# design.net
KiCad netlist of a schematic drawn in Altium Designer
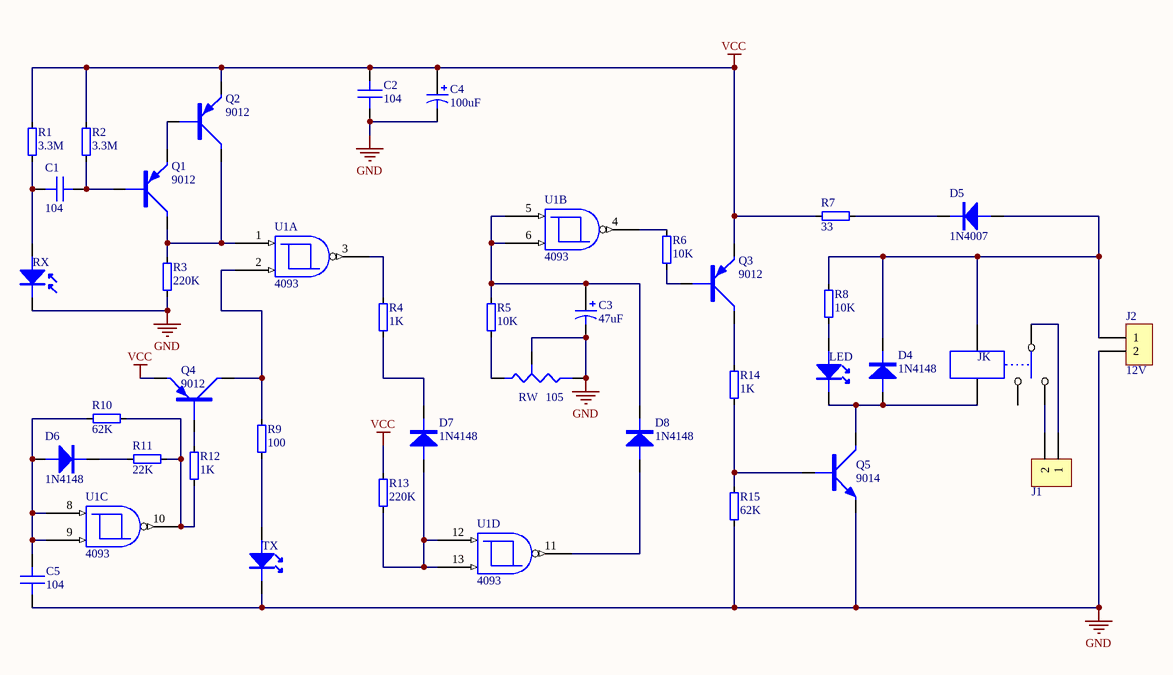
[diagram p0: 红外感应开关.SchDoc]

(export (version "E")
  (design (tool "Eeschema 10.0.6"))
  (components
    (comp (ref "C1")
      (value "CAP")
      (footprint "104独石电容")
      (description "Capacitor，电容")
      (fields (field (name "ALTIUM_UNNAMED_1") "104"))
      (libsource (lib "Backup of 元件") (part "CAP"))
    )
    (comp (ref "C2")
      (value "CAP")
      (footprint "104独石电容")
      (description "Capacitor，电容")
      (fields (field (name "ALTIUM_UNNAMED_1") "104"))
      (libsource (lib "Backup of 元件") (part "CAP"))
    )
    (comp (ref "C3")
      (value "47uF")
      (footprint "47uf")
      (description "Polarized Capacitor (Radial)")
      (fields (field (name "Comment") "Cap Pol1") (field (name "PUBLISHER") "Altium Limited"))
      (libsource (lib "Miscellaneous Devices") (part "Cap Pol1"))
    )
    (comp (ref "C4")
      (value "100uF")
      (footprint "电容D=8mm")
      (description "Polarized Capacitor (Radial)")
      (fields (field (name "Comment") "Cap Pol1") (field (name "PUBLISHER") "Altium Limited"))
      (libsource (lib "Miscellaneous Devices") (part "Cap Pol1"))
    )
    (comp (ref "C5")
      (value "CAP")
      (footprint "104独石电容")
      (description "Capacitor，电容")
      (fields (field (name "ALTIUM_UNNAMED_1") "104"))
      (libsource (lib "Backup of 元件") (part "CAP"))
    )
    (comp (ref "D4") (value "1N4148") (footprint "1N4007") (libsource (lib "DIODE") (part "DIODE")))
    (comp (ref "D5") (value "1N4007") (footprint "1N4007") (libsource (lib "") (part "DIODE_1")))
    (comp (ref "D6") (value "1N4148") (footprint "1N4148") (libsource (lib "") (part "DIODE_2")))
    (comp (ref "D7") (value "1N4148") (footprint "1N4148") (libsource (lib "DIODE") (part "DIODE")))
    (comp (ref "D8") (value "1N4148") (footprint "1N4148") (libsource (lib "DIODE") (part "DIODE")))
    (comp (ref "J1")
      (value "CON2")
      (footprint "KF-5.08")
      (description "Connector")
      (libsource (lib "") (part "CON2_1"))
    )
    (comp (ref "J2")
      (value "12V")
      (footprint "KF-5.08")
      (description "Connector")
      (libsource (lib "MyInt_Lib") (part "CON2"))
    )
    (comp (ref "JK") (value "RWLAY-SPDT") (footprint "继电器") (libsource (lib "J继电器") (part "RWLAY-SPDT")))
    (comp (ref "LED") (value "FA") (footprint "DIODE") (libsource (lib "DIODE") (part "LED")))
    (comp (ref "Q1")
      (value "9012")
      (footprint "8050-TO-92")
      (description "PNP Transistor")
      (libsource (lib "Backup of 元件") (part "9012"))
    )
    (comp (ref "Q2")
      (value "9012")
      (footprint "8050-TO-92")
      (description "PNP Transistor")
      (libsource (lib "Backup of 元件") (part "9012"))
    )
    (comp (ref "Q3")
      (value "9012")
      (footprint "8050-TO-92")
      (description "PNP Transistor")
      (libsource (lib "Backup of 元件") (part "9012"))
    )
    (comp (ref "Q4")
      (value "9012")
      (footprint "8050-TO-92")
      (description "PNP Transistor")
      (libsource (lib "") (part "9012_1"))
    )
    (comp (ref "Q5")
      (value "9014")
      (footprint "8050-TO-92")
      (description "NPN Transistor")
      (libsource (lib "复件 Previous Backup of  元件") (part "9014"))
    )
    (comp (ref "R1")
      (value "RES")
      (footprint "RES-0.25W")
      (fields (field (name "ALTIUM_UNNAMED_1") "3.3M"))
      (libsource (lib "MyInt_Lib") (part "RES"))
    )
    (comp (ref "R2")
      (value "RES")
      (footprint "RES-0.25W")
      (fields (field (name "ALTIUM_UNNAMED_1") "3.3M"))
      (libsource (lib "MyInt_Lib") (part "RES"))
    )
    (comp (ref "R3")
      (value "RES")
      (footprint "RES-0.25W")
      (fields (field (name "ALTIUM_UNNAMED_1") "220K"))
      (libsource (lib "MyInt_Lib") (part "RES"))
    )
    (comp (ref "R4")
      (value "RES")
      (footprint "RES-0.25W")
      (fields (field (name "ALTIUM_UNNAMED_1") "1K"))
      (libsource (lib "MyInt_Lib") (part "RES"))
    )
    (comp (ref "R5")
      (value "RES")
      (footprint "RES-0.25W")
      (fields (field (name "ALTIUM_UNNAMED_1") "10K"))
      (libsource (lib "MyInt_Lib") (part "RES"))
    )
    (comp (ref "R6")
      (value "RES")
      (footprint "RES-0.25W")
      (fields (field (name "ALTIUM_UNNAMED_1") "10K"))
      (libsource (lib "MyInt_Lib") (part "RES"))
    )
    (comp (ref "R7")
      (value "RES")
      (footprint "RES-1W")
      (fields (field (name "ALTIUM_UNNAMED_1") "33"))
      (libsource (lib "MyInt_Lib") (part "RES"))
    )
    (comp (ref "R8")
      (value "RES")
      (footprint "RES-0.25W")
      (fields (field (name "ALTIUM_UNNAMED_1") "10K"))
      (libsource (lib "MyInt_Lib") (part "RES"))
    )
    (comp (ref "R9")
      (value "RES")
      (footprint "RES-1W")
      (fields (field (name "ALTIUM_UNNAMED_1") "100"))
      (libsource (lib "MyInt_Lib") (part "RES"))
    )
    (comp (ref "R10")
      (value "RES")
      (footprint "RES-0.25W")
      (fields (field (name "ALTIUM_UNNAMED_1") "62K"))
      (libsource (lib "MyInt_Lib") (part "RES"))
    )
    (comp (ref "R11")
      (value "RES")
      (footprint "RES-0.25W")
      (fields (field (name "ALTIUM_UNNAMED_1") "22K"))
      (libsource (lib "MyInt_Lib") (part "RES"))
    )
    (comp (ref "R12")
      (value "RES")
      (footprint "RES-0.25W")
      (fields (field (name "ALTIUM_UNNAMED_1") "1K"))
      (libsource (lib "MyInt_Lib") (part "RES"))
    )
    (comp (ref "R13")
      (value "RES")
      (footprint "RES-0.25W")
      (fields (field (name "ALTIUM_UNNAMED_1") "220K"))
      (libsource (lib "MyInt_Lib") (part "RES"))
    )
    (comp (ref "R14")
      (value "RES")
      (footprint "RES-0.25W")
      (fields (field (name "ALTIUM_UNNAMED_1") "1K"))
      (libsource (lib "MyInt_Lib") (part "RES"))
    )
    (comp (ref "R15")
      (value "RES")
      (footprint "RES-0.25W")
      (fields (field (name "ALTIUM_UNNAMED_1") "62K"))
      (libsource (lib "MyInt_Lib") (part "RES"))
    )
    (comp (ref "RW")
      (value "RESISTOR TAPPED")
      (footprint "RVR-2")
      (fields (field (name "ALTIUM_UNNAMED_1") "105"))
      (libsource (lib "MyInt_Lib") (part "RESISTOR TAPPED"))
    )
    (comp (ref "RX")
      (value "SHOU")
      (footprint "红外接受管")
      (description "Photosensitive Diode")
      (libsource (lib "DIODE") (part "PHOTO"))
    )
    (comp (ref "TX") (value "FA") (footprint "DIODE0.1") (libsource (lib "DIODE") (part "LED")))
    (comp (ref "U1") (value "4093") (footprint "DIP-14") (libsource (lib "4000 CMOS") (part "4093")))
  )
  (nets
    (net (code "1") (name "GND") (class "Default")
      (node (ref "C2") (pin "2") (pinfunction "2_2") (pintype "passive"))
      (node (ref "C3") (pin "2") (pinfunction "2_2") (pintype "passive"))
      (node (ref "C4") (pin "2") (pinfunction "2_2") (pintype "passive"))
      (node (ref "C5") (pin "2") (pinfunction "2_2") (pintype "passive"))
      (node (ref "J2") (pin "2") (pinfunction "2_2") (pintype "passive"))
      (node (ref "Q5") (pin "1") (pinfunction "E_1") (pintype "passive"))
      (node (ref "R15") (pin "2") (pinfunction "2_2") (pintype "passive"))
      (node (ref "R3") (pin "2") (pinfunction "2_2") (pintype "passive"))
      (node (ref "RW") (pin "2") (pinfunction "2_2") (pintype "passive"))
      (node (ref "RW") (pin "3") (pinfunction "3_3") (pintype "passive"))
      (node (ref "RX") (pin "2") (pinfunction "2_2") (pintype "passive"))
      (node (ref "TX") (pin "2") (pinfunction "2_2") (pintype "passive"))
      (node (ref "U1") (pin "7") (pinfunction "GND_7") (pintype "power_in"))
    )
    (net (code "2") (name "Net-(C1-Pad2)") (class "Default")
      (node (ref "C1") (pin "2") (pinfunction "2_2") (pintype "passive"))
      (node (ref "R1") (pin "2") (pinfunction "2_2") (pintype "passive"))
      (node (ref "RX") (pin "1") (pinfunction "1_1") (pintype "passive"))
    )
    (net (code "3") (name "Net-(C3-Pad1)") (class "Default")
      (node (ref "C3") (pin "1") (pinfunction "1_1") (pintype "passive"))
      (node (ref "D8") (pin "2") (pinfunction "2_2") (pintype "passive"))
      (node (ref "R5") (pin "1") (pinfunction "1_1") (pintype "passive"))
      (node (ref "U1") (pin "5") (pintype "input"))
      (node (ref "U1") (pin "6") (pintype "input"))
    )
    (net (code "4") (name "Net-(C5-Pad1)") (class "Default")
      (node (ref "C5") (pin "1") (pinfunction "1_1") (pintype "passive"))
      (node (ref "D6") (pin "1") (pinfunction "1_1") (pintype "passive"))
      (node (ref "R10") (pin "1") (pinfunction "1_1") (pintype "passive"))
      (node (ref "U1") (pin "8") (pintype "input"))
      (node (ref "U1") (pin "9") (pintype "input"))
    )
    (net (code "5") (name "Net-(D4-Pad2)") (class "Default")
      (node (ref "D4") (pin "2") (pinfunction "2_2") (pintype "passive"))
      (node (ref "D5") (pin "1") (pinfunction "1_1") (pintype "passive"))
      (node (ref "J2") (pin "1") (pinfunction "1_1") (pintype "passive"))
      (node (ref "JK") (pin "4") (pinfunction "4_4") (pintype "passive"))
      (node (ref "R8") (pin "1") (pinfunction "1_1") (pintype "passive"))
    )
    (net (code "6") (name "Net-(D5-Pad2)") (class "Default")
      (node (ref "D5") (pin "2") (pinfunction "2_2") (pintype "passive"))
      (node (ref "R7") (pin "2") (pinfunction "2_2") (pintype "passive"))
    )
    (net (code "7") (name "Net-(D6-Pad2)") (class "Default")
      (node (ref "D6") (pin "2") (pinfunction "2_2") (pintype "passive"))
      (node (ref "R11") (pin "1") (pinfunction "1_1") (pintype "passive"))
    )
    (net (code "8") (name "Net-(D7-Pad1)") (class "Default")
      (node (ref "D7") (pin "1") (pinfunction "1_1") (pintype "passive"))
      (node (ref "R13") (pin "2") (pinfunction "2_2") (pintype "passive"))
      (node (ref "U1") (pin "12") (pintype "input"))
      (node (ref "U1") (pin "13") (pintype "input"))
    )
    (net (code "9") (name "Net-(D7-Pad2)") (class "Default")
      (node (ref "D7") (pin "2") (pinfunction "2_2") (pintype "passive"))
      (node (ref "R4") (pin "2") (pinfunction "2_2") (pintype "passive"))
    )
    (net (code "10") (name "Net-(D8-Pad1)") (class "Default")
      (node (ref "D8") (pin "1") (pinfunction "1_1") (pintype "passive"))
      (node (ref "U1") (pin "11") (pintype "output"))
    )
    (net (code "11") (name "Net-(J1-Pad1)") (class "Default")
      (node (ref "J1") (pin "1") (pinfunction "1_1") (pintype "passive"))
      (node (ref "JK") (pin "1") (pinfunction "1_1") (pintype "passive"))
    )
    (net (code "12") (name "Net-(J1-Pad2)") (class "Default")
      (node (ref "J1") (pin "2") (pinfunction "2_2") (pintype "passive"))
      (node (ref "JK") (pin "2") (pinfunction "2_2") (pintype "passive"))
    )
    (net (code "13") (name "Net-(LED-Pad1)") (class "Default")
      (node (ref "LED") (pin "1") (pinfunction "1_1") (pintype "passive"))
      (node (ref "R8") (pin "2") (pinfunction "2_2") (pintype "passive"))
    )
    (net (code "14") (name "Net-(Q1-B)") (class "Default")
      (node (ref "C1") (pin "1") (pinfunction "1_1") (pintype "passive"))
      (node (ref "Q1") (pin "2") (pinfunction "B_2") (pintype "passive"))
      (node (ref "R2") (pin "2") (pinfunction "2_2") (pintype "passive"))
    )
    (net (code "15") (name "Net-(Q1-C)") (class "Default")
      (node (ref "Q1") (pin "3") (pinfunction "C_3") (pintype "passive"))
      (node (ref "Q2") (pin "3") (pinfunction "C_3") (pintype "passive"))
      (node (ref "R3") (pin "1") (pinfunction "1_1") (pintype "passive"))
      (node (ref "U1") (pin "1") (pintype "input"))
    )
    (net (code "16") (name "Net-(Q1-E)") (class "Default")
      (node (ref "Q1") (pin "1") (pinfunction "E_1") (pintype "passive"))
      (node (ref "Q2") (pin "2") (pinfunction "B_2") (pintype "passive"))
    )
    (net (code "17") (name "Net-(Q3-B)") (class "Default")
      (node (ref "Q3") (pin "2") (pinfunction "B_2") (pintype "passive"))
      (node (ref "R6") (pin "2") (pinfunction "2_2") (pintype "passive"))
    )
    (net (code "18") (name "Net-(Q3-C)") (class "Default")
      (node (ref "Q3") (pin "3") (pinfunction "C_3") (pintype "passive"))
      (node (ref "R14") (pin "1") (pinfunction "1_1") (pintype "passive"))
    )
    (net (code "19") (name "Net-(Q4-B)") (class "Default")
      (node (ref "Q4") (pin "2") (pinfunction "B_2") (pintype "passive"))
      (node (ref "R12") (pin "1") (pinfunction "1_1") (pintype "passive"))
    )
    (net (code "20") (name "Net-(Q4-C)") (class "Default")
      (node (ref "Q4") (pin "3") (pinfunction "C_3") (pintype "passive"))
      (node (ref "R9") (pin "1") (pinfunction "1_1") (pintype "passive"))
      (node (ref "U1") (pin "2") (pintype "input"))
    )
    (net (code "21") (name "Net-(Q5-B)") (class "Default")
      (node (ref "Q5") (pin "2") (pinfunction "B_2") (pintype "passive"))
      (node (ref "R14") (pin "2") (pinfunction "2_2") (pintype "passive"))
      (node (ref "R15") (pin "1") (pinfunction "1_1") (pintype "passive"))
    )
    (net (code "22") (name "Net-(Q5-C)") (class "Default")
      (node (ref "D4") (pin "1") (pinfunction "1_1") (pintype "passive"))
      (node (ref "JK") (pin "5") (pinfunction "5_5") (pintype "passive"))
      (node (ref "LED") (pin "2") (pinfunction "2_2") (pintype "passive"))
      (node (ref "Q5") (pin "3") (pinfunction "C_3") (pintype "passive"))
    )
    (net (code "23") (name "Net-(R4-Pad1)") (class "Default")
      (node (ref "R4") (pin "1") (pinfunction "1_1") (pintype "passive"))
      (node (ref "U1") (pin "3") (pintype "output"))
    )
    (net (code "24") (name "Net-(R5-Pad2)") (class "Default")
      (node (ref "R5") (pin "2") (pinfunction "2_2") (pintype "passive"))
      (node (ref "RW") (pin "1") (pinfunction "1_1") (pintype "passive"))
    )
    (net (code "25") (name "Net-(R6-Pad1)") (class "Default")
      (node (ref "R6") (pin "1") (pinfunction "1_1") (pintype "passive"))
      (node (ref "U1") (pin "4") (pintype "output"))
    )
    (net (code "26") (name "Net-(R9-Pad2)") (class "Default")
      (node (ref "R9") (pin "2") (pinfunction "2_2") (pintype "passive"))
      (node (ref "TX") (pin "1") (pinfunction "1_1") (pintype "passive"))
    )
    (net (code "27") (name "Net-(R10-Pad2)") (class "Default")
      (node (ref "R10") (pin "2") (pinfunction "2_2") (pintype "passive"))
      (node (ref "R11") (pin "2") (pinfunction "2_2") (pintype "passive"))
      (node (ref "R12") (pin "2") (pinfunction "2_2") (pintype "passive"))
      (node (ref "U1") (pin "10") (pintype "output"))
    )
    (net (code "28") (name "VCC") (class "Default")
      (node (ref "C2") (pin "1") (pinfunction "1_1") (pintype "passive"))
      (node (ref "C4") (pin "1") (pinfunction "1_1") (pintype "passive"))
      (node (ref "Q2") (pin "1") (pinfunction "E_1") (pintype "passive"))
      (node (ref "Q3") (pin "1") (pinfunction "E_1") (pintype "passive"))
      (node (ref "Q4") (pin "1") (pinfunction "E_1") (pintype "passive"))
      (node (ref "R1") (pin "1") (pinfunction "1_1") (pintype "passive"))
      (node (ref "R13") (pin "1") (pinfunction "1_1") (pintype "passive"))
      (node (ref "R2") (pin "1") (pinfunction "1_1") (pintype "passive"))
      (node (ref "R7") (pin "1") (pinfunction "1_1") (pintype "passive"))
      (node (ref "U1") (pin "14") (pinfunction "VCC_14") (pintype "power_in"))
    )
    (net (code "29") (name "unconnected-(JK-Pad3)") (class "Default")
      (node (ref "JK") (pin "3") (pinfunction "3_3") (pintype "passive"))
    )
  )
)
